# CANBUS_USB.net
KiCad netlist of a schematic drawn in EAGLE
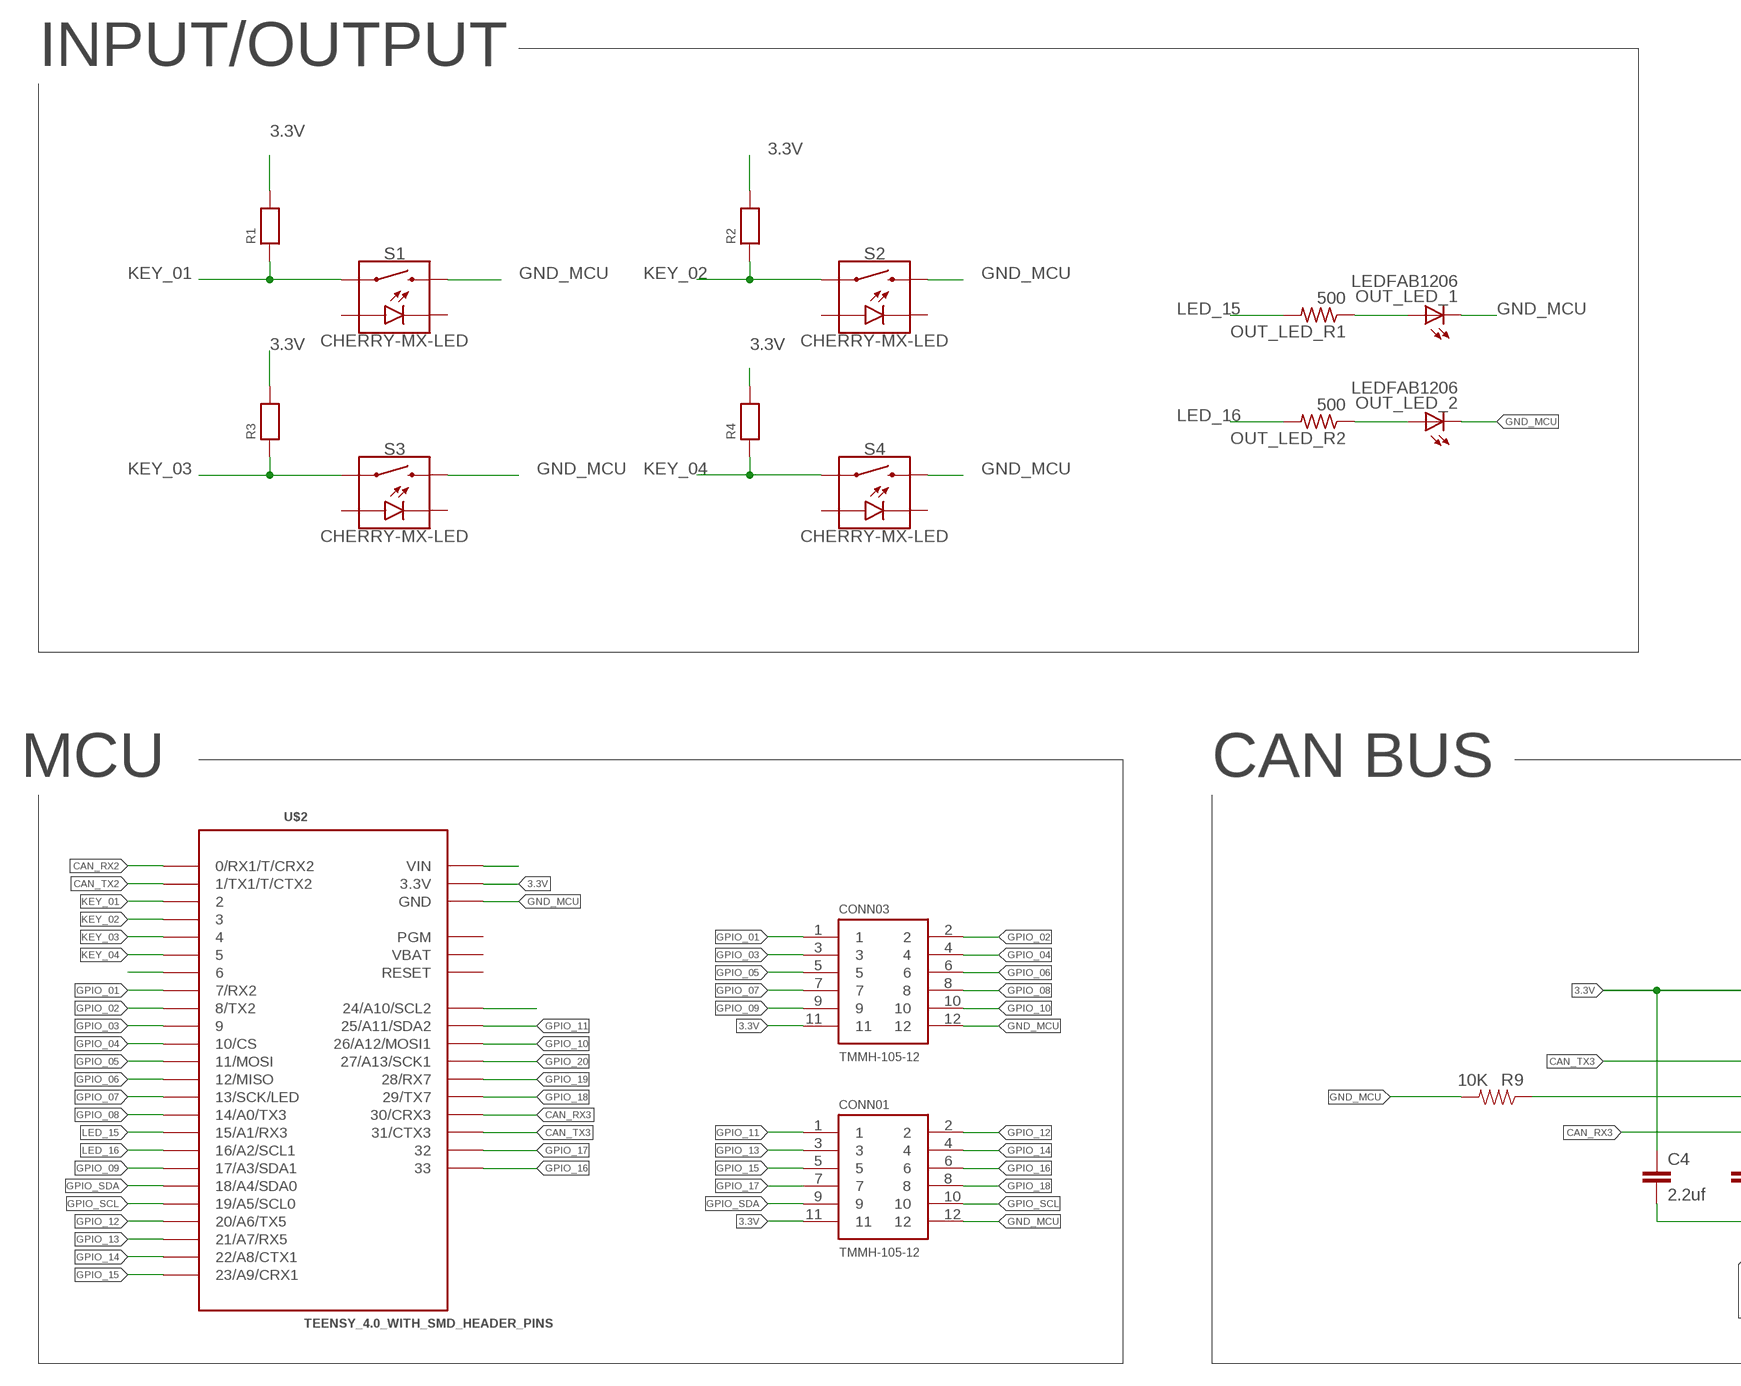
[diagram p0: schematic, sheet 1, part 1 of 2]
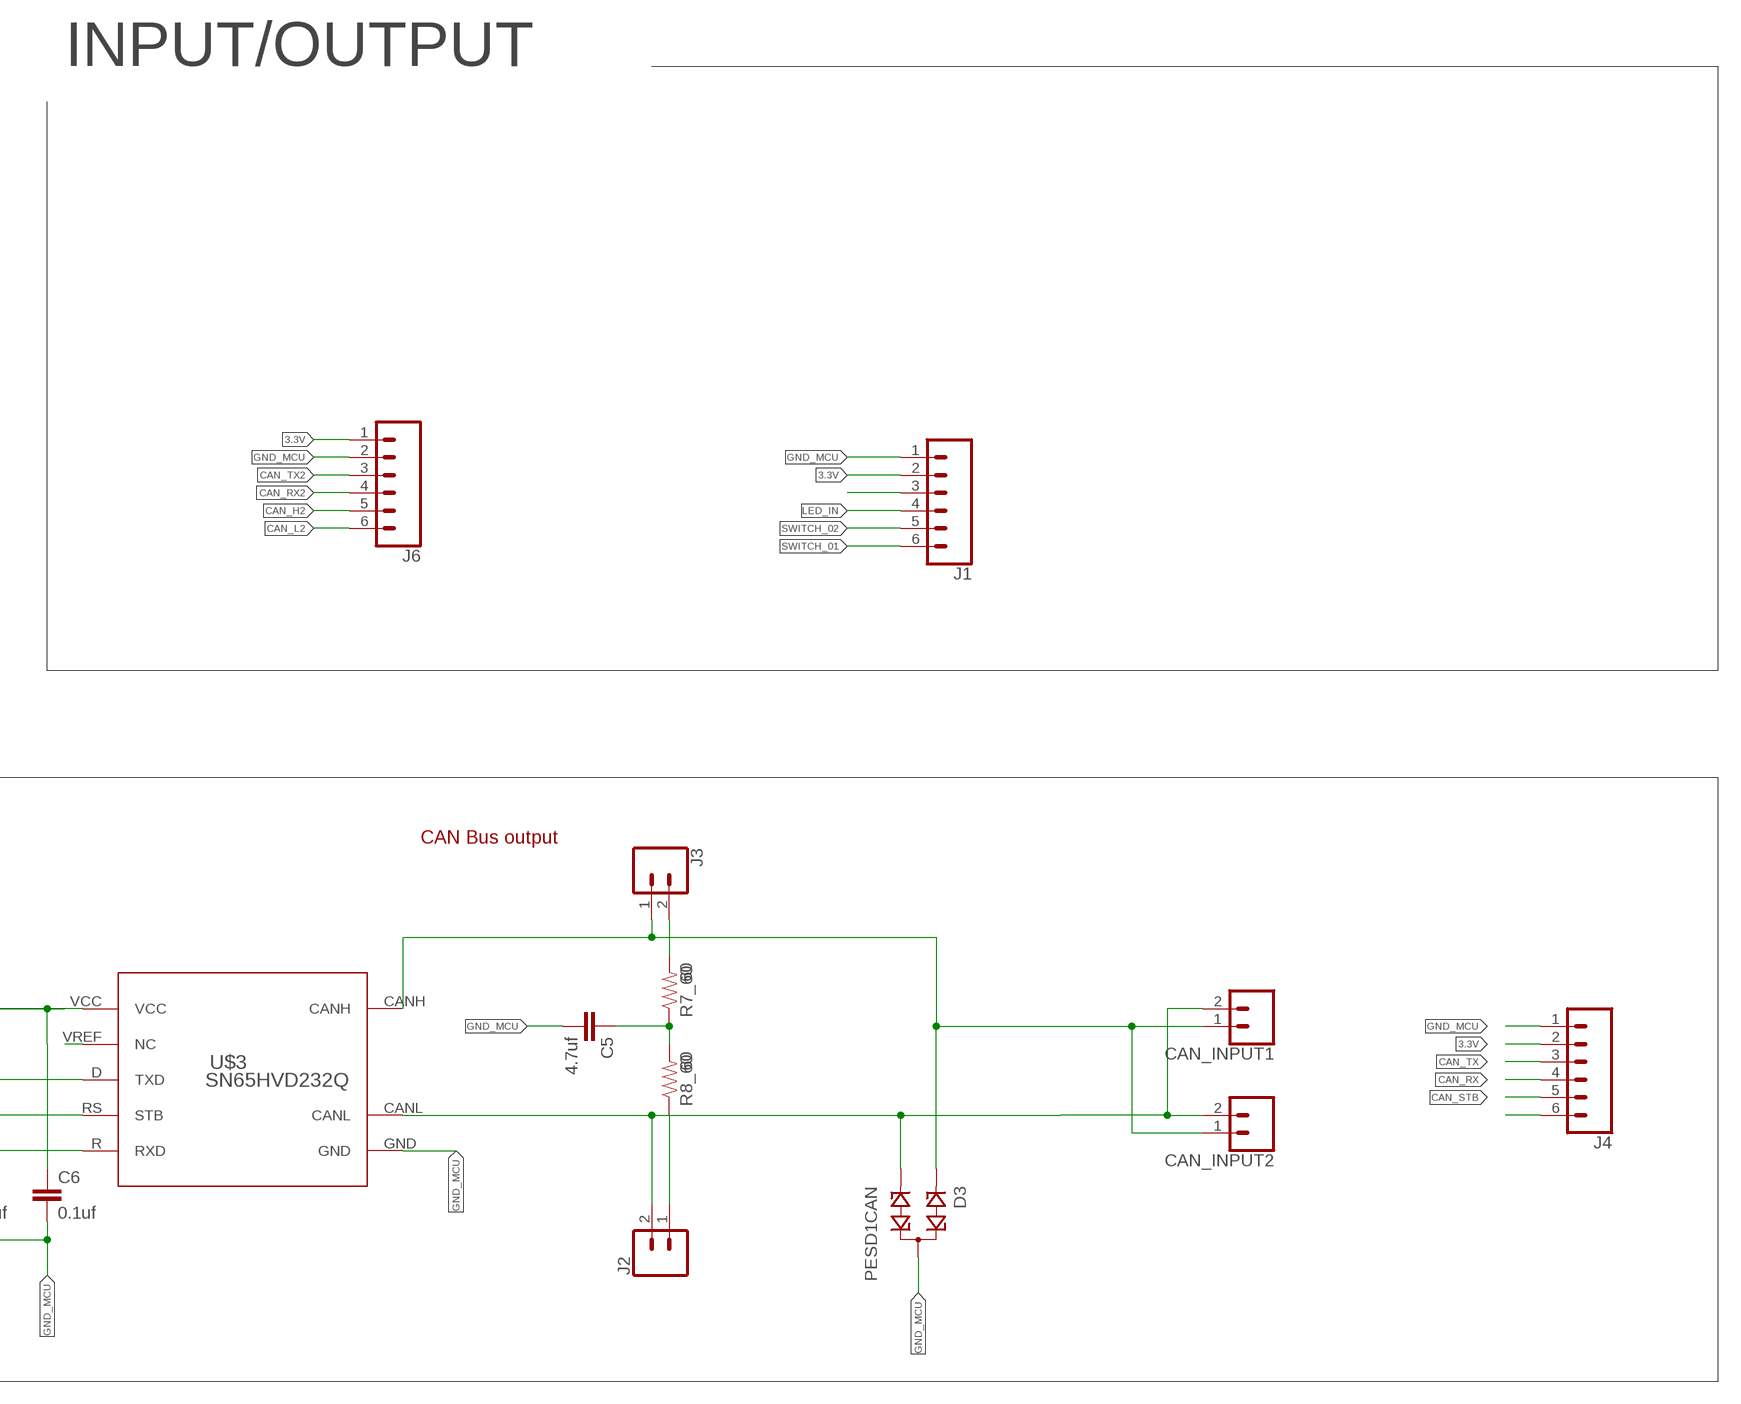
[diagram p1: schematic, sheet 1, part 2 of 2]

(export (version "E")
  (design (tool "Eeschema 10.0.6"))
  (components
    (comp (ref "C4")
      (value "2.2uf")
      (footprint "eagle-import:0603-CAP")
      (libsource (lib "eagle-import") (part "0.1UF-25V(+80/-20%)(0603)"))
    )
    (comp (ref "C5")
      (value "4.7uf")
      (footprint "eagle-import:0603-CAP")
      (libsource (lib "eagle-import") (part "0.1UF-25V(+80/-20%)(0603)"))
    )
    (comp (ref "C6")
      (value "0.1uf")
      (footprint "eagle-import:0603-CAP")
      (libsource (lib "eagle-import") (part "0.1UF-25V(+80/-20%)(0603)"))
    )
    (comp (ref "CAN_INPUT1")
      (value "CONN_02-JST-2MM-SMT")
      (footprint "eagle-import:JST-2-SMD")
      (libsource (lib "eagle-import") (part "CONN_02-JST-2MM-SMT"))
    )
    (comp (ref "CAN_INPUT2")
      (value "CONN_02-JST-2MM-SMT")
      (footprint "eagle-import:JST-2-SMD")
      (libsource (lib "eagle-import") (part "CONN_02-JST-2MM-SMT"))
    )
    (comp (ref "CONN01")
      (value "TMMH-105-12")
      (footprint "eagle-import:TMMH-105-12")
      (libsource (lib "eagle-import") (part "TMMH-105-12"))
    )
    (comp (ref "CONN03")
      (value "TMMH-105-12")
      (footprint "eagle-import:TMMH-105-12")
      (libsource (lib "eagle-import") (part "TMMH-105-12"))
    )
    (comp (ref "D3")
      (value "PESD1CAN")
      (footprint "eagle-import:SOT23")
      (libsource (lib "eagle-import") (part "PESD1CAN"))
    )
    (comp (ref "J1")
      (value "CONN_06SMD-1MM")
      (footprint "eagle-import:1X06-1MM")
      (libsource (lib "eagle-import") (part "CONN_06SMD-1MM"))
    )
    (comp (ref "J2")
      (value "CONN_02")
      (footprint "eagle-import:1X02")
      (libsource (lib "eagle-import") (part "CONN_02"))
    )
    (comp (ref "J3")
      (value "CONN_02")
      (footprint "eagle-import:1X02")
      (libsource (lib "eagle-import") (part "CONN_02"))
    )
    (comp (ref "J4")
      (value "CONN_06SMD-1MM")
      (footprint "eagle-import:1X06-1MM")
      (libsource (lib "eagle-import") (part "CONN_06SMD-1MM"))
    )
    (comp (ref "J6")
      (value "CONN_06NO_SILK_NO_POP")
      (footprint "eagle-import:1X06_NO_SILK")
      (libsource (lib "eagle-import") (part "CONN_06NO_SILK_NO_POP"))
    )
    (comp (ref "OUT_LED_1")
      (value "LEDFAB1206")
      (footprint "eagle-import:LED1206FAB")
      (libsource (lib "eagle-import") (part "LEDFAB1206"))
    )
    (comp (ref "OUT_LED_2")
      (value "LEDFAB1206")
      (footprint "eagle-import:LED1206FAB")
      (libsource (lib "eagle-import") (part "LEDFAB1206"))
    )
    (comp (ref "OUT_LED_R1")
      (value "500")
      (footprint "eagle-import:R1206FAB")
      (libsource (lib "eagle-import") (part "RES-US1206FAB"))
    )
    (comp (ref "OUT_LED_R2")
      (value "500")
      (footprint "eagle-import:R1206FAB")
      (libsource (lib "eagle-import") (part "RES-US1206FAB"))
    )
    (comp (ref "R1")
      (value "RESISTOR1206")
      (footprint "eagle-import:1206")
      (libsource (lib "eagle-import") (part "RESISTOR1206"))
    )
    (comp (ref "R2")
      (value "RESISTOR1206")
      (footprint "eagle-import:1206")
      (libsource (lib "eagle-import") (part "RESISTOR1206"))
    )
    (comp (ref "R3")
      (value "RESISTOR1206")
      (footprint "eagle-import:1206")
      (libsource (lib "eagle-import") (part "RESISTOR1206"))
    )
    (comp (ref "R4")
      (value "RESISTOR1206")
      (footprint "eagle-import:1206")
      (libsource (lib "eagle-import") (part "RESISTOR1206"))
    )
    (comp (ref "R7_60")
      (value "60")
      (footprint "eagle-import:0603-RES")
      (libsource (lib "eagle-import") (part "10KOHM-1/10W-1%(0603)0603"))
    )
    (comp (ref "R8_60")
      (value "60")
      (footprint "eagle-import:0603-RES")
      (libsource (lib "eagle-import") (part "10KOHM-1/10W-1%(0603)0603"))
    )
    (comp (ref "R9")
      (value "10K")
      (footprint "eagle-import:0603-RES")
      (libsource (lib "eagle-import") (part "10KOHM-1/10W-1%(0603)0603"))
    )
    (comp (ref "S1")
      (value "CHERRY-MX-LED")
      (footprint "eagle-import:CHERRY-MX-LED")
      (libsource (lib "eagle-import") (part "CHERRY-MX-LED"))
    )
    (comp (ref "S2")
      (value "CHERRY-MX-LED")
      (footprint "eagle-import:CHERRY-MX-LED")
      (libsource (lib "eagle-import") (part "CHERRY-MX-LED"))
    )
    (comp (ref "S3")
      (value "CHERRY-MX-LED")
      (footprint "eagle-import:CHERRY-MX-LED")
      (libsource (lib "eagle-import") (part "CHERRY-MX-LED"))
    )
    (comp (ref "S4")
      (value "CHERRY-MX-LED")
      (footprint "eagle-import:CHERRY-MX-LED")
      (libsource (lib "eagle-import") (part "CHERRY-MX-LED"))
    )
    (comp (ref "U$2")
      (value "TEENSY_4.0_WITH_SMD_HEADER_PINS")
      (footprint "eagle-import:TEENSY_4.0_WITH_SMD_HEADER_PINS")
      (libsource (lib "eagle-import") (part "TEENSY_4.0_WITH_SMD_HEADER_PINS"))
    )
    (comp (ref "U$3")
      (value "SN65HVD232Q")
      (footprint "eagle-import:SN65HVD232Q")
      (libsource (lib "eagle-import") (part "SN65HVD232Q"))
    )
  )
  (nets
    (net (code "1") (name "/VBAT") (class "Default")
      (node (ref "U$2") (pin "VBAT") (pinfunction "VBAT_VBAT") (pintype "power_in"))
    )
    (net (code "2") (name "3.3V") (class "Default")
      (node (ref "C4") (pin "1") (pinfunction "1_1") (pintype "passive"))
      (node (ref "C6") (pin "1") (pinfunction "1_1") (pintype "passive"))
      (node (ref "CONN01") (pin "11") (pinfunction "11_11") (pintype "bidirectional"))
      (node (ref "CONN03") (pin "11") (pinfunction "11_11") (pintype "bidirectional"))
      (node (ref "J1") (pin "2") (pinfunction "2_2") (pintype "passive"))
      (node (ref "J4") (pin "2") (pinfunction "2_2") (pintype "passive"))
      (node (ref "J6") (pin "1") (pinfunction "1_1") (pintype "passive"))
      (node (ref "R1") (pin "2") (pinfunction "2_2") (pintype "passive"))
      (node (ref "R2") (pin "2") (pinfunction "2_2") (pintype "passive"))
      (node (ref "R3") (pin "2") (pinfunction "2_2") (pintype "passive"))
      (node (ref "R4") (pin "2") (pinfunction "2_2") (pintype "passive"))
      (node (ref "U$2") (pin "3.3V") (pinfunction "3.3V_3.3V") (pintype "power_in"))
      (node (ref "U$2") (pin "3.3V1") (pinfunction "3.3V_3.3V1") (pintype "power_in"))
      (node (ref "U$3") (pin "VCC") (pinfunction "VCC_VCC") (pintype "power_in"))
    )
    (net (code "3") (name "CAN_H2") (class "Default")
      (node (ref "J6") (pin "5") (pinfunction "5_5") (pintype "passive"))
    )
    (net (code "4") (name "CAN_L2") (class "Default")
      (node (ref "J6") (pin "6") (pinfunction "6_6") (pintype "passive"))
    )
    (net (code "5") (name "CAN_RX") (class "Default")
      (node (ref "J4") (pin "4") (pinfunction "4_4") (pintype "passive"))
    )
    (net (code "6") (name "CAN_RX2") (class "Default")
      (node (ref "J6") (pin "4") (pinfunction "4_4") (pintype "passive"))
      (node (ref "U$2") (pin "0") (pinfunction "0/RX1/T/CRX2_0") (pintype "bidirectional"))
    )
    (net (code "7") (name "CAN_RX3") (class "Default")
      (node (ref "U$2") (pin "30") (pinfunction "30/CRX3_30") (pintype "bidirectional"))
      (node (ref "U$3") (pin "R") (pinfunction "RXD_R") (pintype "output"))
    )
    (net (code "8") (name "CAN_STB") (class "Default")
      (node (ref "J4") (pin "5") (pinfunction "5_5") (pintype "passive"))
    )
    (net (code "9") (name "CAN_TX") (class "Default")
      (node (ref "J1") (pin "3") (pinfunction "3_3") (pintype "passive"))
      (node (ref "J4") (pin "3") (pinfunction "3_3") (pintype "passive"))
    )
    (net (code "10") (name "CAN_TX2") (class "Default")
      (node (ref "J6") (pin "3") (pinfunction "3_3") (pintype "passive"))
      (node (ref "U$2") (pin "1") (pinfunction "1/TX1/T/CTX2_1") (pintype "bidirectional"))
    )
    (net (code "11") (name "CAN_TX3") (class "Default")
      (node (ref "U$2") (pin "31") (pinfunction "31/CTX3_31") (pintype "bidirectional"))
      (node (ref "U$3") (pin "D") (pinfunction "TXD_D") (pintype "input"))
    )
    (net (code "12") (name "GND_MCU") (class "Default")
      (node (ref "C4") (pin "2") (pinfunction "2_2") (pintype "passive"))
      (node (ref "C5") (pin "2") (pinfunction "2_2") (pintype "passive"))
      (node (ref "C6") (pin "2") (pinfunction "2_2") (pintype "passive"))
      (node (ref "CONN01") (pin "12") (pinfunction "12_12") (pintype "bidirectional"))
      (node (ref "CONN03") (pin "12") (pinfunction "12_12") (pintype "bidirectional"))
      (node (ref "D3") (pin "3") (pinfunction "3_3") (pintype "passive"))
      (node (ref "J1") (pin "1") (pinfunction "1_1") (pintype "passive"))
      (node (ref "J4") (pin "1") (pinfunction "1_1") (pintype "passive"))
      (node (ref "J6") (pin "2") (pinfunction "2_2") (pintype "passive"))
      (node (ref "OUT_LED_1") (pin "2") (pinfunction "C_2") (pintype "passive"))
      (node (ref "OUT_LED_2") (pin "2") (pinfunction "C_2") (pintype "passive"))
      (node (ref "R9") (pin "2") (pinfunction "2_2") (pintype "passive"))
      (node (ref "S1") (pin "S2") (pinfunction "S2_S2") (pintype "passive"))
      (node (ref "S2") (pin "S2") (pinfunction "S2_S2") (pintype "passive"))
      (node (ref "S3") (pin "S2") (pinfunction "S2_S2") (pintype "passive"))
      (node (ref "S4") (pin "S2") (pinfunction "S2_S2") (pintype "passive"))
      (node (ref "U$2") (pin "GND") (pinfunction "GND_GND") (pintype "power_in"))
      (node (ref "U$2") (pin "GND1") (pinfunction "GND_GND1") (pintype "power_in"))
      (node (ref "U$2") (pin "GND2") (pinfunction "GND_GND2") (pintype "power_in"))
      (node (ref "U$3") (pin "GND") (pinfunction "GND_GND") (pintype "power_in"))
    )
    (net (code "13") (name "GPIO_01") (class "Default")
      (node (ref "CONN03") (pin "1") (pinfunction "1_1") (pintype "bidirectional"))
      (node (ref "U$2") (pin "7") (pinfunction "7/RX2_7") (pintype "bidirectional"))
    )
    (net (code "14") (name "GPIO_02") (class "Default")
      (node (ref "CONN03") (pin "2") (pinfunction "2_2") (pintype "bidirectional"))
      (node (ref "U$2") (pin "8") (pinfunction "8/TX2_8") (pintype "bidirectional"))
    )
    (net (code "15") (name "GPIO_03") (class "Default")
      (node (ref "CONN03") (pin "3") (pinfunction "3_3") (pintype "bidirectional"))
      (node (ref "U$2") (pin "9") (pinfunction "9_9") (pintype "bidirectional"))
    )
    (net (code "16") (name "GPIO_04") (class "Default")
      (node (ref "CONN03") (pin "4") (pinfunction "4_4") (pintype "bidirectional"))
      (node (ref "U$2") (pin "10") (pinfunction "10/CS_10") (pintype "bidirectional"))
    )
    (net (code "17") (name "GPIO_05") (class "Default")
      (node (ref "CONN03") (pin "5") (pinfunction "5_5") (pintype "bidirectional"))
      (node (ref "U$2") (pin "11") (pinfunction "11/MOSI_11") (pintype "bidirectional"))
    )
    (net (code "18") (name "GPIO_06") (class "Default")
      (node (ref "CONN03") (pin "6") (pinfunction "6_6") (pintype "bidirectional"))
      (node (ref "U$2") (pin "12") (pinfunction "12/MISO_12") (pintype "bidirectional"))
    )
    (net (code "19") (name "GPIO_07") (class "Default")
      (node (ref "CONN03") (pin "7") (pinfunction "7_7") (pintype "bidirectional"))
      (node (ref "U$2") (pin "13") (pinfunction "13/SCK/LED_13") (pintype "bidirectional"))
    )
    (net (code "20") (name "GPIO_08") (class "Default")
      (node (ref "CONN03") (pin "8") (pinfunction "8_8") (pintype "bidirectional"))
      (node (ref "U$2") (pin "14/A0") (pinfunction "14/A0/TX3_14/A0") (pintype "bidirectional"))
    )
    (net (code "21") (name "GPIO_09") (class "Default")
      (node (ref "CONN03") (pin "9") (pinfunction "9_9") (pintype "bidirectional"))
      (node (ref "U$2") (pin "17/A3") (pinfunction "17/A3/SDA1_17/A3") (pintype "bidirectional"))
    )
    (net (code "22") (name "GPIO_10") (class "Default")
      (node (ref "CONN03") (pin "10") (pinfunction "10_10") (pintype "bidirectional"))
      (node (ref "U$2") (pin "26") (pinfunction "26/A12/MOSI1_26") (pintype "bidirectional"))
    )
    (net (code "23") (name "GPIO_11") (class "Default")
      (node (ref "CONN01") (pin "1") (pinfunction "1_1") (pintype "bidirectional"))
      (node (ref "U$2") (pin "25") (pinfunction "25/A11/SDA2_25") (pintype "bidirectional"))
    )
    (net (code "24") (name "GPIO_12") (class "Default")
      (node (ref "CONN01") (pin "2") (pinfunction "2_2") (pintype "bidirectional"))
      (node (ref "U$2") (pin "20/A6") (pinfunction "20/A6/TX5_20/A6") (pintype "bidirectional"))
    )
    (net (code "25") (name "GPIO_13") (class "Default")
      (node (ref "CONN01") (pin "3") (pinfunction "3_3") (pintype "bidirectional"))
      (node (ref "U$2") (pin "21/A7") (pinfunction "21/A7/RX5_21/A7") (pintype "bidirectional"))
    )
    (net (code "26") (name "GPIO_14") (class "Default")
      (node (ref "CONN01") (pin "4") (pinfunction "4_4") (pintype "bidirectional"))
      (node (ref "U$2") (pin "22/A8") (pinfunction "22/A8/CTX1_22/A8") (pintype "bidirectional"))
    )
    (net (code "27") (name "GPIO_15") (class "Default")
      (node (ref "CONN01") (pin "5") (pinfunction "5_5") (pintype "bidirectional"))
      (node (ref "U$2") (pin "23/A9") (pinfunction "23/A9/CRX1_23/A9") (pintype "bidirectional"))
    )
    (net (code "28") (name "GPIO_16") (class "Default")
      (node (ref "CONN01") (pin "6") (pinfunction "6_6") (pintype "bidirectional"))
      (node (ref "U$2") (pin "33") (pinfunction "33_33") (pintype "bidirectional"))
    )
    (net (code "29") (name "GPIO_17") (class "Default")
      (node (ref "CONN01") (pin "7") (pinfunction "7_7") (pintype "bidirectional"))
      (node (ref "U$2") (pin "32") (pinfunction "32_32") (pintype "bidirectional"))
    )
    (net (code "30") (name "GPIO_18") (class "Default")
      (node (ref "CONN01") (pin "8") (pinfunction "8_8") (pintype "bidirectional"))
      (node (ref "U$2") (pin "29") (pinfunction "29/TX7_29") (pintype "bidirectional"))
    )
    (net (code "31") (name "GPIO_19") (class "Default")
      (node (ref "U$2") (pin "28") (pinfunction "28/RX7_28") (pintype "bidirectional"))
    )
    (net (code "32") (name "GPIO_20") (class "Default")
      (node (ref "U$2") (pin "27") (pinfunction "27/A13/SCK1_27") (pintype "bidirectional"))
    )
    (net (code "33") (name "GPIO_SCL") (class "Default")
      (node (ref "CONN01") (pin "10") (pinfunction "10_10") (pintype "bidirectional"))
      (node (ref "U$2") (pin "19/A5") (pinfunction "19/A5/SCL0_19/A5") (pintype "bidirectional"))
    )
    (net (code "34") (name "GPIO_SDA") (class "Default")
      (node (ref "CONN01") (pin "9") (pinfunction "9_9") (pintype "bidirectional"))
      (node (ref "U$2") (pin "18/A4") (pinfunction "18/A4/SDA0_18/A4") (pintype "bidirectional"))
    )
    (net (code "35") (name "KEY_01") (class "Default")
      (node (ref "R1") (pin "1") (pinfunction "1_1") (pintype "passive"))
      (node (ref "S1") (pin "S1") (pinfunction "S1_S1") (pintype "passive"))
      (node (ref "U$2") (pin "2") (pinfunction "2_2") (pintype "bidirectional"))
    )
    (net (code "36") (name "KEY_02") (class "Default")
      (node (ref "R2") (pin "1") (pinfunction "1_1") (pintype "passive"))
      (node (ref "S2") (pin "S1") (pinfunction "S1_S1") (pintype "passive"))
      (node (ref "U$2") (pin "3") (pinfunction "3_3") (pintype "bidirectional"))
    )
    (net (code "37") (name "KEY_03") (class "Default")
      (node (ref "R3") (pin "1") (pinfunction "1_1") (pintype "passive"))
      (node (ref "S3") (pin "S1") (pinfunction "S1_S1") (pintype "passive"))
      (node (ref "U$2") (pin "4") (pinfunction "4_4") (pintype "bidirectional"))
    )
    (net (code "38") (name "KEY_04") (class "Default")
      (node (ref "R4") (pin "1") (pinfunction "1_1") (pintype "passive"))
      (node (ref "S4") (pin "S1") (pinfunction "S1_S1") (pintype "passive"))
      (node (ref "U$2") (pin "5") (pinfunction "5_5") (pintype "bidirectional"))
    )
    (net (code "39") (name "LED_15") (class "Default")
      (node (ref "OUT_LED_R1") (pin "2") (pinfunction "2_2") (pintype "passive"))
      (node (ref "U$2") (pin "15/A1") (pinfunction "15/A1/RX3_15/A1") (pintype "bidirectional"))
    )
    (net (code "40") (name "LED_16") (class "Default")
      (node (ref "OUT_LED_R2") (pin "2") (pinfunction "2_2") (pintype "passive"))
      (node (ref "U$2") (pin "16/A2") (pinfunction "16/A2/SCL1_16/A2") (pintype "bidirectional"))
    )
    (net (code "41") (name "LED_IN") (class "Default")
      (node (ref "J1") (pin "4") (pinfunction "4_4") (pintype "passive"))
    )
    (net (code "42") (name "Net-(C5-Pad1)") (class "Default")
      (node (ref "C5") (pin "1") (pinfunction "1_1") (pintype "passive"))
      (node (ref "R7_60") (pin "1") (pinfunction "1_1") (pintype "passive"))
      (node (ref "R8_60") (pin "2") (pinfunction "2_2") (pintype "passive"))
    )
    (net (code "43") (name "Net-(CAN_INPUT1-1)") (class "Default")
      (node (ref "CAN_INPUT1") (pin "2") (pinfunction "1_2") (pintype "passive"))
      (node (ref "CAN_INPUT2") (pin "2") (pinfunction "1_2") (pintype "passive"))
      (node (ref "D3") (pin "2") (pinfunction "2_2") (pintype "passive"))
      (node (ref "J2") (pin "2") (pinfunction "2_2") (pintype "passive"))
      (node (ref "U$3") (pin "CANL") (pinfunction "CANL_CANL") (pintype "bidirectional"))
    )
    (net (code "44") (name "Net-(CAN_INPUT1-2)") (class "Default")
      (node (ref "CAN_INPUT1") (pin "1") (pinfunction "2_1") (pintype "passive"))
      (node (ref "CAN_INPUT2") (pin "1") (pinfunction "2_1") (pintype "passive"))
      (node (ref "D3") (pin "1") (pinfunction "1_1") (pintype "passive"))
      (node (ref "J3") (pin "1") (pinfunction "1_1") (pintype "passive"))
      (node (ref "U$3") (pin "CANH") (pinfunction "CANH_CANH") (pintype "bidirectional"))
    )
    (net (code "45") (name "Net-(J2-Pad1)") (class "Default")
      (node (ref "J2") (pin "1") (pinfunction "1_1") (pintype "passive"))
      (node (ref "R8_60") (pin "1") (pinfunction "1_1") (pintype "passive"))
    )
    (net (code "46") (name "Net-(J3-Pad2)") (class "Default")
      (node (ref "J3") (pin "2") (pinfunction "2_2") (pintype "passive"))
      (node (ref "R7_60") (pin "2") (pinfunction "2_2") (pintype "passive"))
    )
    (net (code "47") (name "Net-(OUT_LED_1-A)") (class "Default")
      (node (ref "OUT_LED_1") (pin "1") (pinfunction "A_1") (pintype "passive"))
      (node (ref "OUT_LED_R1") (pin "1") (pinfunction "1_1") (pintype "passive"))
    )
    (net (code "48") (name "Net-(OUT_LED_2-A)") (class "Default")
      (node (ref "OUT_LED_2") (pin "1") (pinfunction "A_1") (pintype "passive"))
      (node (ref "OUT_LED_R2") (pin "1") (pinfunction "1_1") (pintype "passive"))
    )
    (net (code "49") (name "Net-(U$3-STB)") (class "Default")
      (node (ref "R9") (pin "1") (pinfunction "1_1") (pintype "passive"))
      (node (ref "U$3") (pin "RS") (pinfunction "STB_RS") (pintype "input"))
    )
    (net (code "50") (name "SWITCH_01") (class "Default")
      (node (ref "J1") (pin "6") (pinfunction "6_6") (pintype "passive"))
    )
    (net (code "51") (name "SWITCH_02") (class "Default")
      (node (ref "J1") (pin "5") (pinfunction "5_5") (pintype "passive"))
    )
    (net (code "52") (name "unconnected-(J4-Pad6)") (class "Default")
      (node (ref "J4") (pin "6") (pinfunction "6_6") (pintype "passive"))
    )
    (net (code "53") (name "unconnected-(S1-C-PadK)") (class "Default")
      (node (ref "S1") (pin "K") (pinfunction "C_K") (pintype "passive"))
    )
    (net (code "54") (name "unconnected-(S1-PadA)") (class "Default")
      (node (ref "S1") (pin "A") (pinfunction "A_A") (pintype "passive"))
    )
    (net (code "55") (name "unconnected-(S2-C-PadK)") (class "Default")
      (node (ref "S2") (pin "K") (pinfunction "C_K") (pintype "passive"))
    )
    (net (code "56") (name "unconnected-(S2-PadA)") (class "Default")
      (node (ref "S2") (pin "A") (pinfunction "A_A") (pintype "passive"))
    )
    (net (code "57") (name "unconnected-(S3-C-PadK)") (class "Default")
      (node (ref "S3") (pin "K") (pinfunction "C_K") (pintype "passive"))
    )
    (net (code "58") (name "unconnected-(S3-PadA)") (class "Default")
      (node (ref "S3") (pin "A") (pinfunction "A_A") (pintype "passive"))
    )
    (net (code "59") (name "unconnected-(S4-C-PadK)") (class "Default")
      (node (ref "S4") (pin "K") (pinfunction "C_K") (pintype "passive"))
    )
    (net (code "60") (name "unconnected-(S4-PadA)") (class "Default")
      (node (ref "S4") (pin "A") (pinfunction "A_A") (pintype "passive"))
    )
    (net (code "61") (name "unconnected-(U$2-24{slash}A10{slash}SCL2-Pad24)") (class "Default")
      (node (ref "U$2") (pin "24") (pinfunction "24/A10/SCL2_24") (pintype "bidirectional"))
    )
    (net (code "62") (name "unconnected-(U$2-Pad6)") (class "Default")
      (node (ref "U$2") (pin "6") (pinfunction "6_6") (pintype "bidirectional"))
    )
    (net (code "63") (name "unconnected-(U$2-PadPGM)") (class "Default")
      (node (ref "U$2") (pin "PGM") (pinfunction "PGM_PGM") (pintype "bidirectional"))
    )
    (net (code "64") (name "unconnected-(U$2-PadRESET)") (class "Default")
      (node (ref "U$2") (pin "RESET") (pinfunction "RESET_RESET") (pintype "bidirectional"))
    )
    (net (code "65") (name "unconnected-(U$2-PadVIN)") (class "Default")
      (node (ref "U$2") (pin "VIN") (pinfunction "VIN_VIN") (pintype "power_in"))
    )
    (net (code "66") (name "unconnected-(U$3-NC-PadVREF)") (class "Default")
      (node (ref "U$3") (pin "VREF") (pinfunction "NC_VREF") (pintype "passive"))
    )
  )
)
